# pce_pll.net
KiCad netlist of a schematic drawn in EAGLE
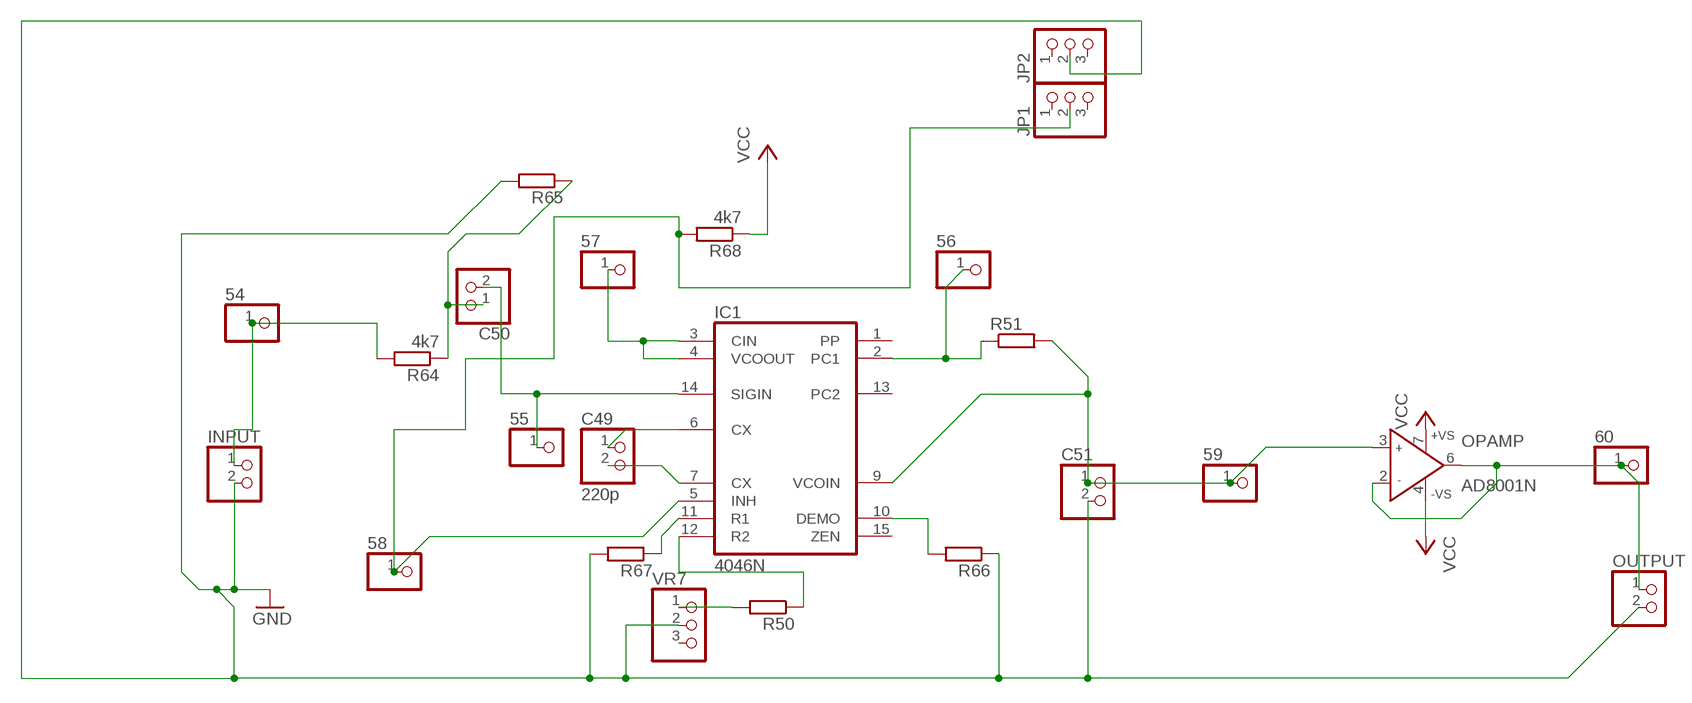
[diagram p0: schematic, sheet 1]

(export (version "E")
  (design (tool "Eeschema 10.0.6"))
  (components
    (comp (ref "54")
      (value "PINHD-1X1")
      (footprint "eagle-import:1X01")
      (libsource (lib "eagle-import") (part "PINHD-1X1"))
    )
    (comp (ref "55")
      (value "PINHD-1X1")
      (footprint "eagle-import:1X01")
      (libsource (lib "eagle-import") (part "PINHD-1X1"))
    )
    (comp (ref "56")
      (value "PINHD-1X1")
      (footprint "eagle-import:1X01")
      (libsource (lib "eagle-import") (part "PINHD-1X1"))
    )
    (comp (ref "57")
      (value "PINHD-1X1")
      (footprint "eagle-import:1X01")
      (libsource (lib "eagle-import") (part "PINHD-1X1"))
    )
    (comp (ref "58")
      (value "PINHD-1X1")
      (footprint "eagle-import:1X01")
      (libsource (lib "eagle-import") (part "PINHD-1X1"))
    )
    (comp (ref "59")
      (value "PINHD-1X1")
      (footprint "eagle-import:1X01")
      (libsource (lib "eagle-import") (part "PINHD-1X1"))
    )
    (comp (ref "60")
      (value "PINHD-1X1")
      (footprint "eagle-import:1X01")
      (libsource (lib "eagle-import") (part "PINHD-1X1"))
    )
    (comp (ref "C49")
      (value "220p")
      (footprint "eagle-import:1X02")
      (libsource (lib "eagle-import") (part "PINHD-1X2"))
    )
    (comp (ref "C50")
      (value "PINHD-1X2")
      (footprint "eagle-import:1X02")
      (libsource (lib "eagle-import") (part "PINHD-1X2"))
    )
    (comp (ref "C51")
      (value "PINHD-1X2")
      (footprint "eagle-import:1X02")
      (libsource (lib "eagle-import") (part "PINHD-1X2"))
    )
    (comp (ref "IC1")
      (value "4046N")
      (footprint "eagle-import:DIL16")
      (libsource (lib "eagle-import") (part "4046N"))
    )
    (comp (ref "INPUT")
      (value "PINHD-1X2")
      (footprint "eagle-import:1X02")
      (libsource (lib "eagle-import") (part "PINHD-1X2"))
    )
    (comp (ref "JP1")
      (value "PINHD-1X3")
      (footprint "eagle-import:1X03")
      (libsource (lib "eagle-import") (part "PINHD-1X3"))
    )
    (comp (ref "JP2")
      (value "PINHD-1X3")
      (footprint "eagle-import:1X03")
      (libsource (lib "eagle-import") (part "PINHD-1X3"))
    )
    (comp (ref "OPAMP")
      (value "AD8001N")
      (footprint "eagle-import:DIL08")
      (fields (field (name "MPN") "AD8001ANZ"))
      (libsource (lib "eagle-import") (part "AD8001N"))
    )
    (comp (ref "OUTPUT")
      (value "PINHD-1X2")
      (footprint "eagle-import:1X02")
      (libsource (lib "eagle-import") (part "PINHD-1X2"))
    )
    (comp (ref "R50")
      (value "R-EU_0207/10")
      (footprint "eagle-import:0207_10")
      (libsource (lib "eagle-import") (part "R-EU_0207/10"))
    )
    (comp (ref "R51")
      (value "R-EU_0207/10")
      (footprint "eagle-import:0207_10")
      (libsource (lib "eagle-import") (part "R-EU_0207/10"))
    )
    (comp (ref "R64")
      (value "4k7")
      (footprint "eagle-import:0207_10")
      (libsource (lib "eagle-import") (part "R-EU_0207/10"))
    )
    (comp (ref "R65")
      (value "R-EU_0207/10")
      (footprint "eagle-import:0207_10")
      (libsource (lib "eagle-import") (part "R-EU_0207/10"))
    )
    (comp (ref "R66")
      (value "R-EU_0207/10")
      (footprint "eagle-import:0207_10")
      (libsource (lib "eagle-import") (part "R-EU_0207/10"))
    )
    (comp (ref "R67")
      (value "R-EU_0207/10")
      (footprint "eagle-import:0207_10")
      (libsource (lib "eagle-import") (part "R-EU_0207/10"))
    )
    (comp (ref "R68")
      (value "4k7")
      (footprint "eagle-import:0207_10")
      (libsource (lib "eagle-import") (part "R-EU_0207/10"))
    )
    (comp (ref "VR7")
      (value "PINHD-1X3")
      (footprint "eagle-import:1X03")
      (libsource (lib "eagle-import") (part "PINHD-1X3"))
    )
  )
  (nets
    (net (code "1") (name "GND") (class "Default")
      (node (ref "C51") (pin "2") (pinfunction "2_2") (pintype "passive"))
      (node (ref "INPUT") (pin "2") (pinfunction "2_2") (pintype "passive"))
      (node (ref "JP2") (pin "2") (pinfunction "2_2") (pintype "passive"))
      (node (ref "OUTPUT") (pin "2") (pinfunction "2_2") (pintype "passive"))
      (node (ref "R65") (pin "2") (pinfunction "2_2") (pintype "passive"))
      (node (ref "R66") (pin "1") (pinfunction "1_1") (pintype "passive"))
      (node (ref "R67") (pin "2") (pinfunction "2_2") (pintype "passive"))
      (node (ref "VR7") (pin "2") (pinfunction "2_2") (pintype "passive"))
    )
    (net (code "2") (name "Net-(54-Pad1)") (class "Default")
      (node (ref "54") (pin "1") (pinfunction "1_1") (pintype "passive"))
      (node (ref "INPUT") (pin "1") (pinfunction "1_1") (pintype "passive"))
      (node (ref "R64") (pin "2") (pinfunction "2_2") (pintype "passive"))
    )
    (net (code "3") (name "Net-(C49-Pad1)") (class "Default")
      (node (ref "C49") (pin "1") (pinfunction "1_1") (pintype "passive"))
      (node (ref "IC1") (pin "6") (pinfunction "CX_6") (pintype "input"))
    )
    (net (code "4") (name "Net-(C49-Pad2)") (class "Default")
      (node (ref "C49") (pin "2") (pinfunction "2_2") (pintype "passive"))
      (node (ref "IC1") (pin "7") (pinfunction "CX_7") (pintype "input"))
    )
    (net (code "5") (name "Net-(C50-Pad1)") (class "Default")
      (node (ref "C50") (pin "1") (pinfunction "1_1") (pintype "passive"))
      (node (ref "R64") (pin "1") (pinfunction "1_1") (pintype "passive"))
      (node (ref "R65") (pin "1") (pinfunction "1_1") (pintype "passive"))
    )
    (net (code "6") (name "Net-(IC1A-CIN)") (class "Default")
      (node (ref "57") (pin "1") (pinfunction "1_1") (pintype "passive"))
      (node (ref "IC1") (pin "3") (pinfunction "CIN_3") (pintype "input"))
      (node (ref "IC1") (pin "4") (pinfunction "VCOOUT_4") (pintype "output"))
    )
    (net (code "7") (name "Net-(IC1A-DEMO)") (class "Default")
      (node (ref "IC1") (pin "10") (pinfunction "DEMO_10") (pintype "output"))
      (node (ref "R66") (pin "2") (pinfunction "2_2") (pintype "passive"))
    )
    (net (code "8") (name "Net-(IC1A-INH)") (class "Default")
      (node (ref "58") (pin "1") (pinfunction "1_1") (pintype "passive"))
      (node (ref "IC1") (pin "5") (pinfunction "INH_5") (pintype "input"))
      (node (ref "JP1") (pin "2") (pinfunction "2_2") (pintype "passive"))
      (node (ref "R68") (pin "2") (pinfunction "2_2") (pintype "passive"))
    )
    (net (code "9") (name "Net-(IC1A-PC1)") (class "Default")
      (node (ref "56") (pin "1") (pinfunction "1_1") (pintype "passive"))
      (node (ref "IC1") (pin "2") (pinfunction "PC1_2") (pintype "output"))
      (node (ref "R51") (pin "1") (pinfunction "1_1") (pintype "passive"))
    )
    (net (code "10") (name "Net-(IC1A-R1)") (class "Default")
      (node (ref "IC1") (pin "11") (pinfunction "R1_11") (pintype "input"))
      (node (ref "R67") (pin "1") (pinfunction "1_1") (pintype "passive"))
    )
    (net (code "11") (name "Net-(IC1A-R2)") (class "Default")
      (node (ref "IC1") (pin "12") (pinfunction "R2_12") (pintype "input"))
      (node (ref "R50") (pin "1") (pinfunction "1_1") (pintype "passive"))
    )
    (net (code "12") (name "Net-(IC1A-SIGIN)") (class "Default")
      (node (ref "55") (pin "1") (pinfunction "1_1") (pintype "passive"))
      (node (ref "C50") (pin "2") (pinfunction "2_2") (pintype "passive"))
      (node (ref "IC1") (pin "14") (pinfunction "SIGIN_14") (pintype "input"))
    )
    (net (code "13") (name "Net-(IC1A-VCOIN)") (class "Default")
      (node (ref "59") (pin "1") (pinfunction "1_1") (pintype "passive"))
      (node (ref "C51") (pin "1") (pinfunction "1_1") (pintype "passive"))
      (node (ref "IC1") (pin "9") (pinfunction "VCOIN_9") (pintype "input"))
      (node (ref "OPAMP") (pin "3") (pinfunction "IN+_3") (pintype "input"))
      (node (ref "R51") (pin "2") (pinfunction "2_2") (pintype "passive"))
    )
    (net (code "14") (name "Net-(OPAMP-IN-)") (class "Default")
      (node (ref "60") (pin "1") (pinfunction "1_1") (pintype "passive"))
      (node (ref "OPAMP") (pin "2") (pinfunction "IN-_2") (pintype "input"))
      (node (ref "OPAMP") (pin "6") (pinfunction "OUT_6") (pintype "output"))
      (node (ref "OUTPUT") (pin "1") (pinfunction "1_1") (pintype "passive"))
    )
    (net (code "15") (name "Net-(R50-Pad2)") (class "Default")
      (node (ref "R50") (pin "2") (pinfunction "2_2") (pintype "passive"))
      (node (ref "VR7") (pin "1") (pinfunction "1_1") (pintype "passive"))
    )
    (net (code "16") (name "VCC") (class "Default")
      (node (ref "OPAMP") (pin "4") (pinfunction "-VS_4") (pintype "input"))
      (node (ref "OPAMP") (pin "7") (pinfunction "+VS_7") (pintype "input"))
      (node (ref "R68") (pin "1") (pinfunction "1_1") (pintype "passive"))
    )
    (net (code "17") (name "unconnected-(IC1A-PC2-Pad13)") (class "Default")
      (node (ref "IC1") (pin "13") (pinfunction "PC2_13") (pintype "output"))
    )
    (net (code "18") (name "unconnected-(IC1A-PP-Pad1)") (class "Default")
      (node (ref "IC1") (pin "1") (pinfunction "PP_1") (pintype "output"))
    )
    (net (code "19") (name "unconnected-(IC1A-ZEN-Pad15)") (class "Default")
      (node (ref "IC1") (pin "15") (pinfunction "ZEN_15") (pintype "input"))
    )
    (net (code "20") (name "unconnected-(JP1-Pad1)") (class "Default")
      (node (ref "JP1") (pin "1") (pinfunction "1_1") (pintype "passive"))
    )
    (net (code "21") (name "unconnected-(JP1-Pad3)") (class "Default")
      (node (ref "JP1") (pin "3") (pinfunction "3_3") (pintype "passive"))
    )
    (net (code "22") (name "unconnected-(JP2-Pad1)") (class "Default")
      (node (ref "JP2") (pin "1") (pinfunction "1_1") (pintype "passive"))
    )
    (net (code "23") (name "unconnected-(JP2-Pad3)") (class "Default")
      (node (ref "JP2") (pin "3") (pinfunction "3_3") (pintype "passive"))
    )
    (net (code "24") (name "unconnected-(VR7-Pad3)") (class "Default")
      (node (ref "VR7") (pin "3") (pinfunction "3_3") (pintype "passive"))
    )
  )
)
